# VHDCI.net
KiCad netlist of a schematic drawn in Altium Designer
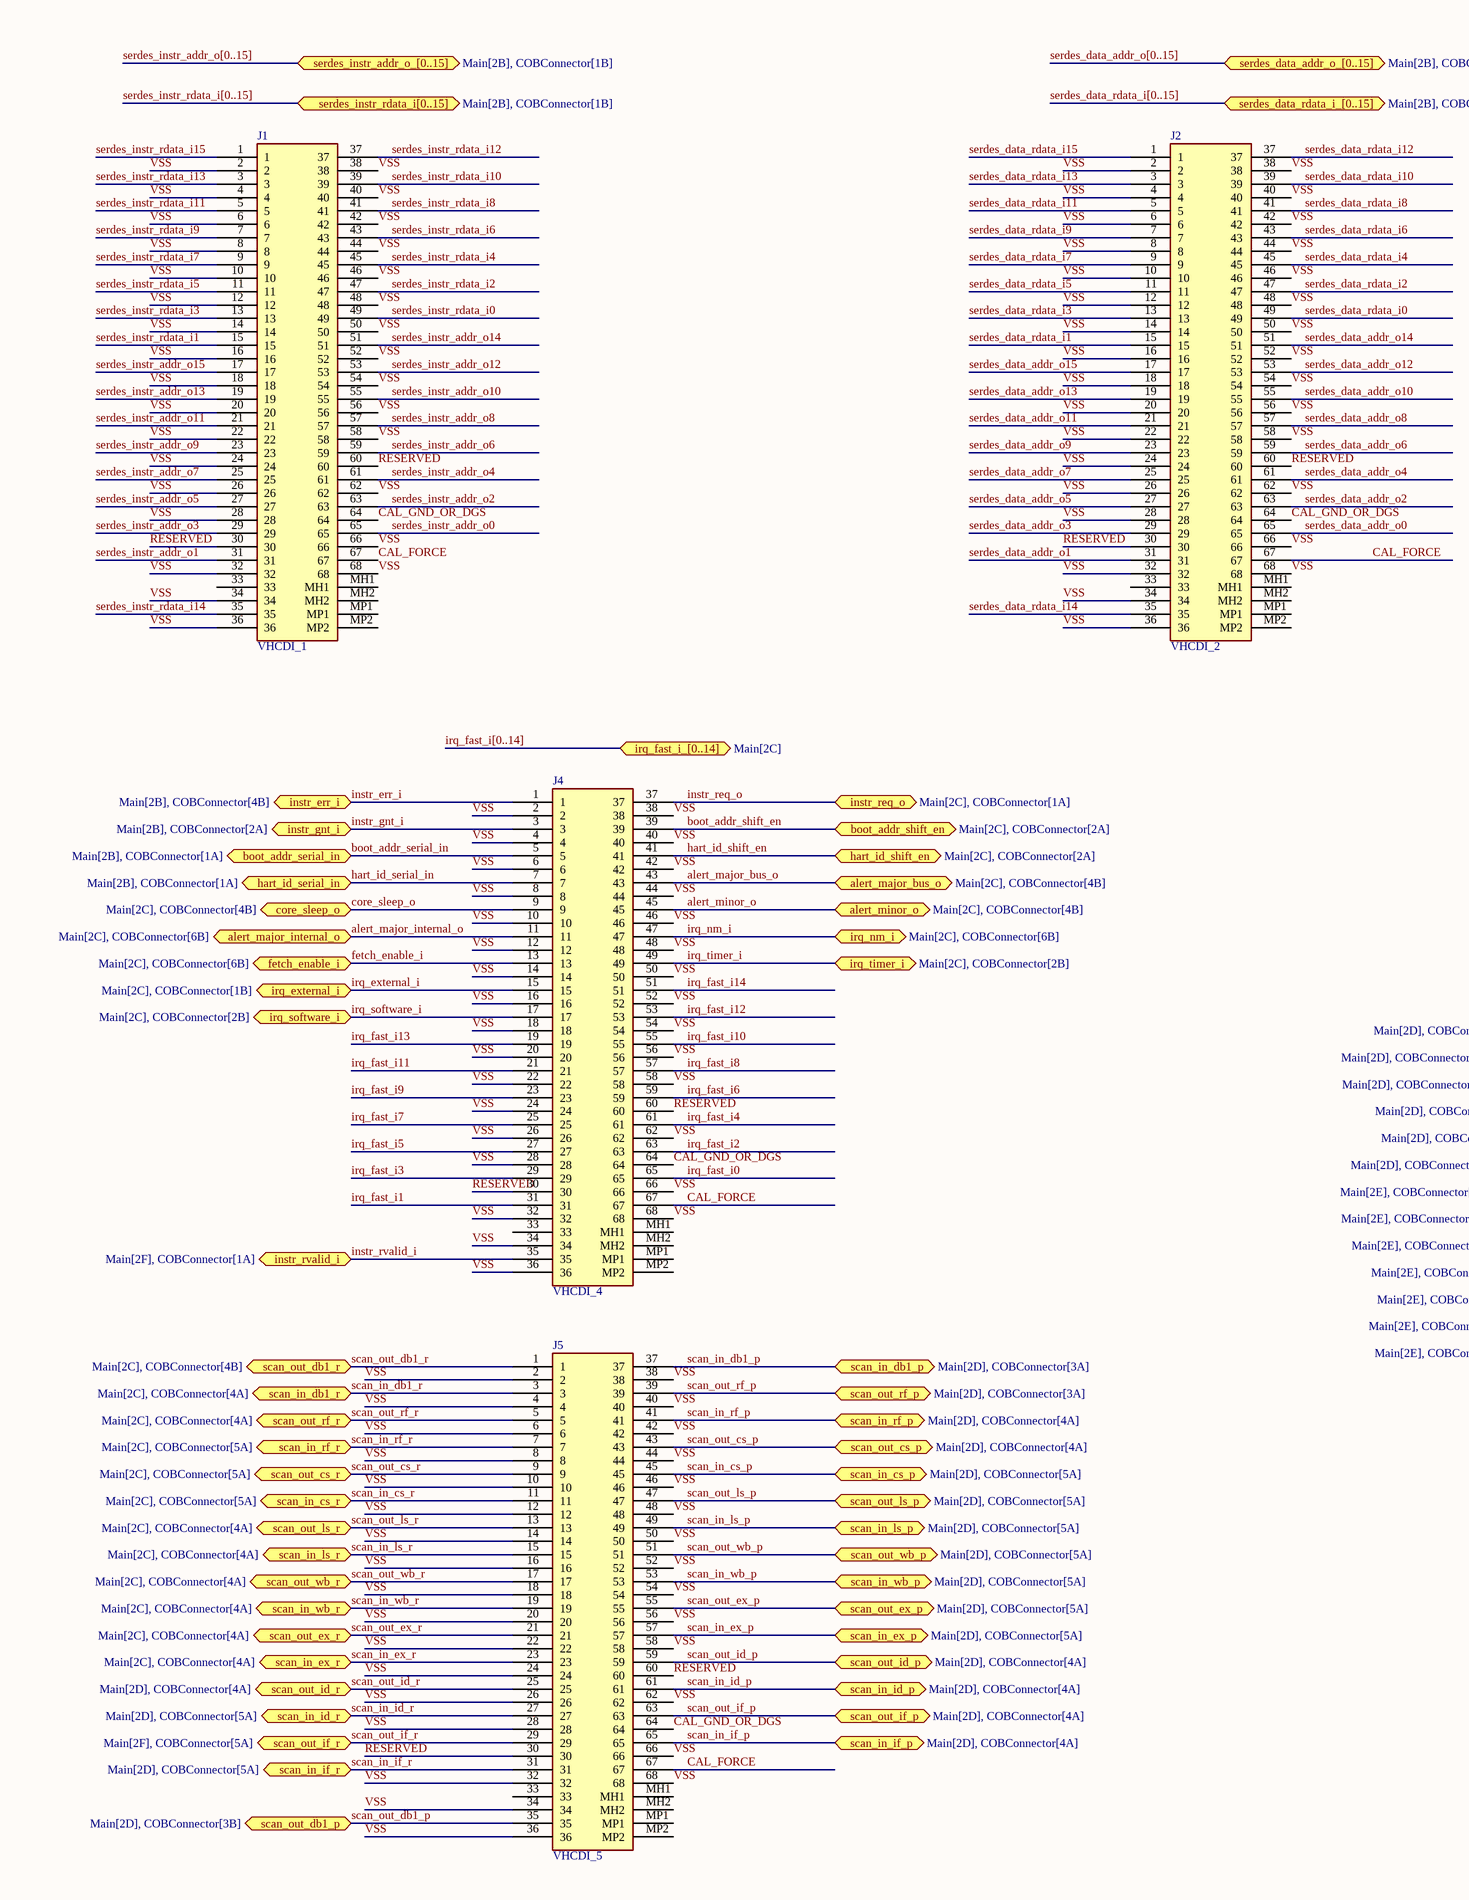
[diagram p0: VHDCI.SchDoc, left]
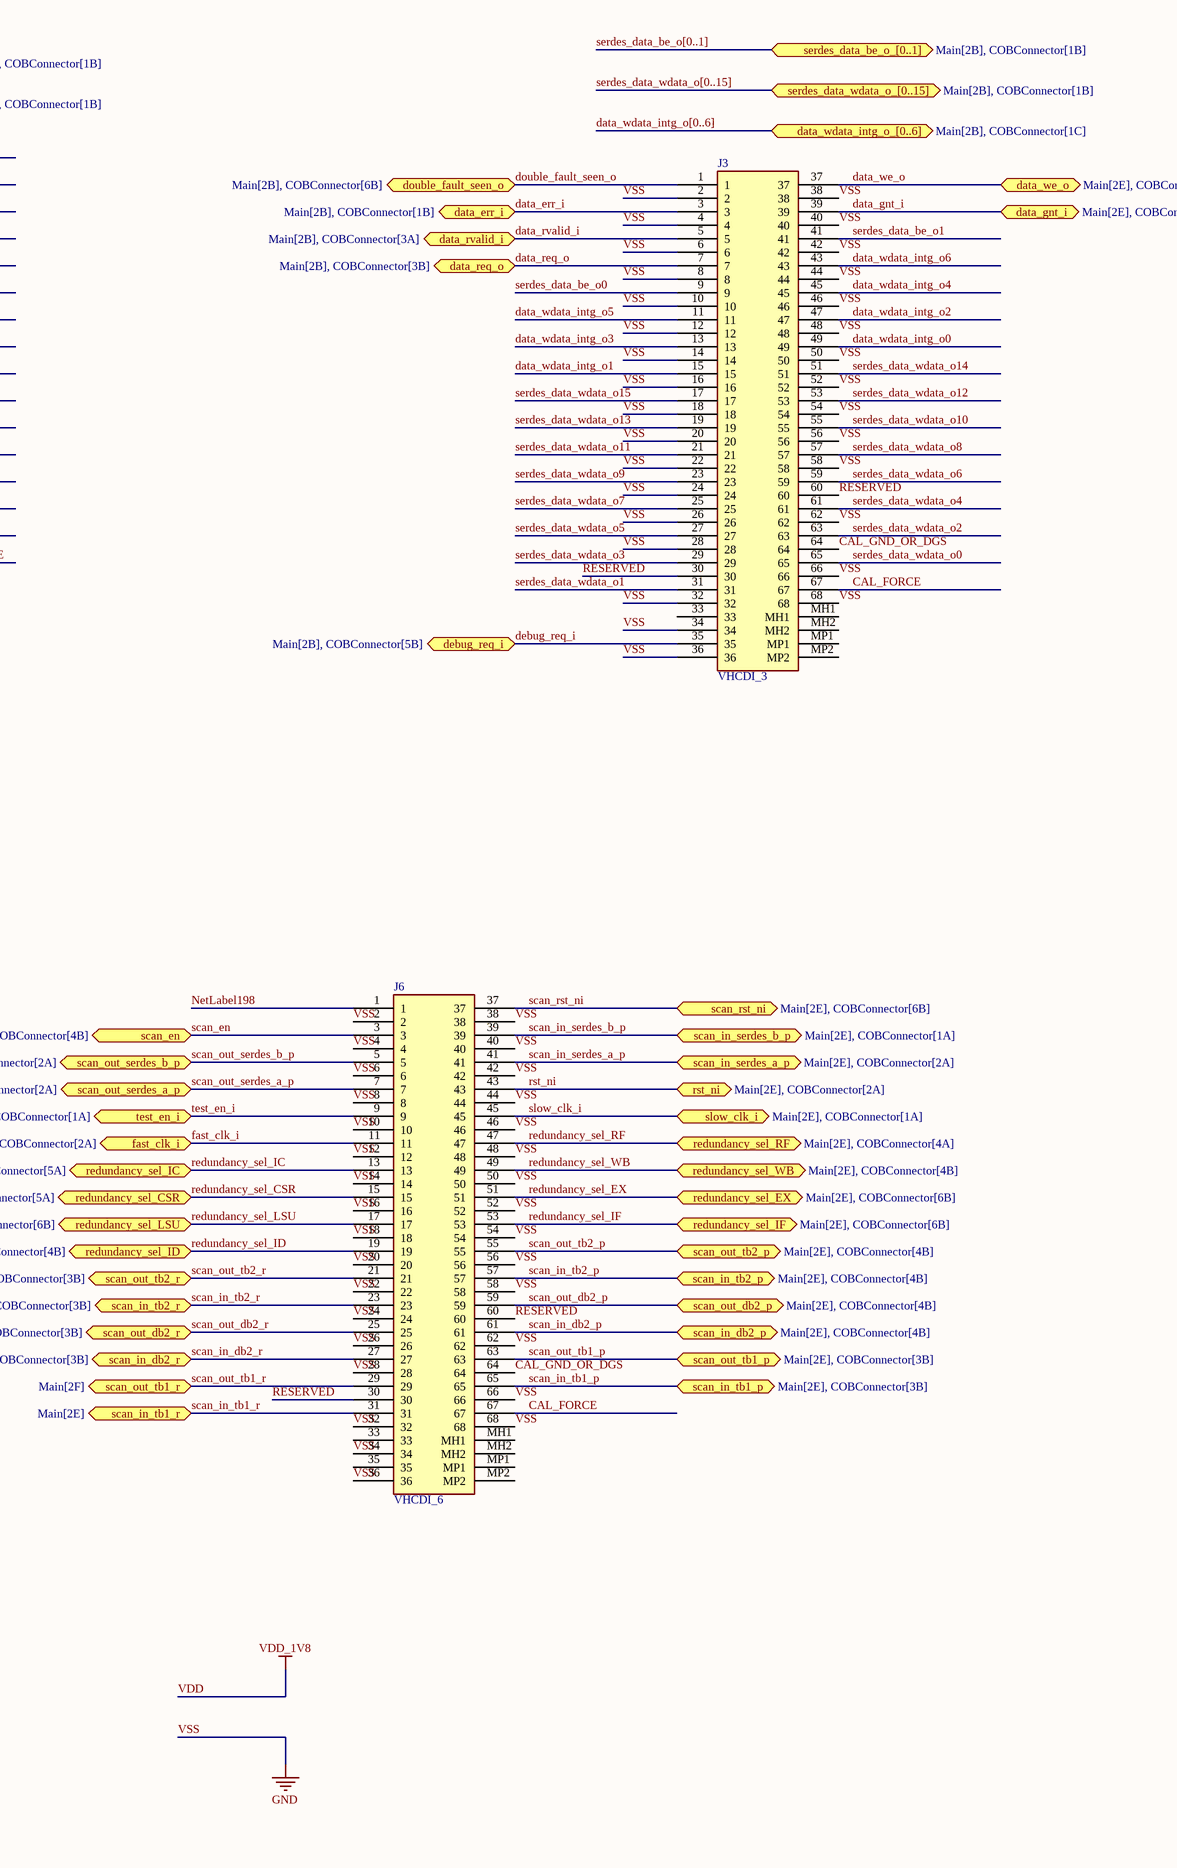
[diagram p1: VHDCI.SchDoc, right]

(export (version "E")
  (design (tool "Eeschema 10.0.6"))
  (components
    (comp (ref "J1")
      (value "VHCDI_1")
      (footprint "CONN68_HDRA-EC_HON")
      (description "Connector")
      (fields (field (name "MANUFACTURER_PART_NUMBER") "785633-01"))
      (libsource (lib "00-100001-001") (part "785633-01"))
    )
    (comp (ref "J2")
      (value "VHCDI_2")
      (footprint "CONN68_HDRA-EC_HON")
      (description "Connector")
      (fields (field (name "MANUFACTURER_PART_NUMBER") "785633-01"))
      (libsource (lib "00-100001-001") (part "785633-01"))
    )
    (comp (ref "J3")
      (value "VHCDI_3")
      (footprint "CONN68_HDRA-EC_HON")
      (description "Connector")
      (fields (field (name "MANUFACTURER_PART_NUMBER") "785633-01"))
      (libsource (lib "00-100001-001") (part "785633-01"))
    )
    (comp (ref "J4")
      (value "VHCDI_4")
      (footprint "CONN68_HDRA-EC_HON")
      (description "Connector")
      (fields (field (name "MANUFACTURER_PART_NUMBER") "785633-01"))
      (libsource (lib "00-100001-001") (part "785633-01"))
    )
    (comp (ref "J5")
      (value "VHCDI_5")
      (footprint "CONN68_HDRA-EC_HON")
      (description "Connector")
      (fields (field (name "MANUFACTURER_PART_NUMBER") "785633-01"))
      (libsource (lib "00-100001-001") (part "785633-01"))
    )
    (comp (ref "J6")
      (value "VHCDI_6")
      (footprint "CONN68_HDRA-EC_HON")
      (description "Connector")
      (fields (field (name "MANUFACTURER_PART_NUMBER") "785633-01"))
      (libsource (lib "00-100001-001") (part "785633-01"))
    )
  )
  (nets
    (net (code "1") (name "/CAL_FORCE") (class "Default")
      (node (ref "J1") (pin "67") (pinfunction "67_67") (pintype "passive"))
      (node (ref "J2") (pin "67") (pinfunction "67_67") (pintype "passive"))
      (node (ref "J3") (pin "67") (pinfunction "67_67") (pintype "passive"))
      (node (ref "J4") (pin "67") (pinfunction "67_67") (pintype "passive"))
      (node (ref "J5") (pin "67") (pinfunction "67_67") (pintype "passive"))
      (node (ref "J6") (pin "67") (pinfunction "67_67") (pintype "passive"))
    )
    (net (code "2") (name "/CAL_GND_OR_DGS") (class "Default")
      (node (ref "J1") (pin "64") (pinfunction "64_64") (pintype "passive"))
      (node (ref "J2") (pin "64") (pinfunction "64_64") (pintype "passive"))
      (node (ref "J3") (pin "64") (pinfunction "64_64") (pintype "passive"))
      (node (ref "J4") (pin "64") (pinfunction "64_64") (pintype "passive"))
      (node (ref "J5") (pin "64") (pinfunction "64_64") (pintype "passive"))
      (node (ref "J6") (pin "64") (pinfunction "64_64") (pintype "passive"))
    )
    (net (code "3") (name "/NetLabel198") (class "Default")
      (node (ref "J6") (pin "1") (pinfunction "1_1") (pintype "passive"))
    )
    (net (code "4") (name "/RESERVED") (class "Default")
      (node (ref "J1") (pin "30") (pinfunction "30_30") (pintype "passive"))
      (node (ref "J1") (pin "60") (pinfunction "60_60") (pintype "passive"))
      (node (ref "J2") (pin "30") (pinfunction "30_30") (pintype "passive"))
      (node (ref "J2") (pin "60") (pinfunction "60_60") (pintype "passive"))
      (node (ref "J3") (pin "30") (pinfunction "30_30") (pintype "passive"))
      (node (ref "J3") (pin "60") (pinfunction "60_60") (pintype "passive"))
      (node (ref "J4") (pin "30") (pinfunction "30_30") (pintype "passive"))
      (node (ref "J4") (pin "60") (pinfunction "60_60") (pintype "passive"))
      (node (ref "J5") (pin "30") (pinfunction "30_30") (pintype "passive"))
      (node (ref "J5") (pin "60") (pinfunction "60_60") (pintype "passive"))
      (node (ref "J6") (pin "30") (pinfunction "30_30") (pintype "passive"))
      (node (ref "J6") (pin "60") (pinfunction "60_60") (pintype "passive"))
    )
    (net (code "5") (name "/alert_major_bus_o") (class "Default")
      (node (ref "J4") (pin "43") (pinfunction "43_43") (pintype "passive"))
    )
    (net (code "6") (name "/alert_major_internal_o") (class "Default")
      (node (ref "J4") (pin "11") (pinfunction "11_11") (pintype "passive"))
    )
    (net (code "7") (name "/alert_minor_o") (class "Default")
      (node (ref "J4") (pin "45") (pinfunction "45_45") (pintype "passive"))
    )
    (net (code "8") (name "/boot_addr_serial_in") (class "Default")
      (node (ref "J4") (pin "5") (pinfunction "5_5") (pintype "passive"))
    )
    (net (code "9") (name "/boot_addr_shift_en") (class "Default")
      (node (ref "J4") (pin "39") (pinfunction "39_39") (pintype "passive"))
    )
    (net (code "10") (name "/core_sleep_o") (class "Default")
      (node (ref "J4") (pin "9") (pinfunction "9_9") (pintype "passive"))
    )
    (net (code "11") (name "/data_err_i") (class "Default")
      (node (ref "J3") (pin "3") (pinfunction "3_3") (pintype "passive"))
    )
    (net (code "12") (name "/data_gnt_i") (class "Default")
      (node (ref "J3") (pin "39") (pinfunction "39_39") (pintype "passive"))
    )
    (net (code "13") (name "/data_req_o") (class "Default")
      (node (ref "J3") (pin "7") (pinfunction "7_7") (pintype "passive"))
    )
    (net (code "14") (name "/data_rvalid_i") (class "Default")
      (node (ref "J3") (pin "5") (pinfunction "5_5") (pintype "passive"))
    )
    (net (code "15") (name "/data_wdata_intg_o0") (class "Default")
      (node (ref "J3") (pin "49") (pinfunction "49_49") (pintype "passive"))
    )
    (net (code "16") (name "/data_wdata_intg_o1") (class "Default")
      (node (ref "J3") (pin "15") (pinfunction "15_15") (pintype "passive"))
    )
    (net (code "17") (name "/data_wdata_intg_o2") (class "Default")
      (node (ref "J3") (pin "47") (pinfunction "47_47") (pintype "passive"))
    )
    (net (code "18") (name "/data_wdata_intg_o3") (class "Default")
      (node (ref "J3") (pin "13") (pinfunction "13_13") (pintype "passive"))
    )
    (net (code "19") (name "/data_wdata_intg_o4") (class "Default")
      (node (ref "J3") (pin "45") (pinfunction "45_45") (pintype "passive"))
    )
    (net (code "20") (name "/data_wdata_intg_o5") (class "Default")
      (node (ref "J3") (pin "11") (pinfunction "11_11") (pintype "passive"))
    )
    (net (code "21") (name "/data_wdata_intg_o6") (class "Default")
      (node (ref "J3") (pin "43") (pinfunction "43_43") (pintype "passive"))
    )
    (net (code "23") (name "/data_we_o") (class "Default")
      (node (ref "J3") (pin "37") (pinfunction "37_37") (pintype "passive"))
    )
    (net (code "24") (name "/debug_req_i") (class "Default")
      (node (ref "J3") (pin "35") (pinfunction "35_35") (pintype "passive"))
    )
    (net (code "25") (name "/double_fault_seen_o") (class "Default")
      (node (ref "J3") (pin "1") (pinfunction "1_1") (pintype "passive"))
    )
    (net (code "26") (name "/fast_clk_i") (class "Default")
      (node (ref "J6") (pin "11") (pinfunction "11_11") (pintype "passive"))
    )
    (net (code "27") (name "/fetch_enable_i") (class "Default")
      (node (ref "J4") (pin "13") (pinfunction "13_13") (pintype "passive"))
    )
    (net (code "28") (name "/hart_id_serial_in") (class "Default")
      (node (ref "J4") (pin "7") (pinfunction "7_7") (pintype "passive"))
    )
    (net (code "29") (name "/hart_id_shift_en") (class "Default")
      (node (ref "J4") (pin "41") (pinfunction "41_41") (pintype "passive"))
    )
    (net (code "30") (name "/instr_err_i") (class "Default")
      (node (ref "J4") (pin "1") (pinfunction "1_1") (pintype "passive"))
    )
    (net (code "31") (name "/instr_gnt_i") (class "Default")
      (node (ref "J4") (pin "3") (pinfunction "3_3") (pintype "passive"))
    )
    (net (code "32") (name "/instr_req_o") (class "Default")
      (node (ref "J4") (pin "37") (pinfunction "37_37") (pintype "passive"))
    )
    (net (code "33") (name "/instr_rvalid_i") (class "Default")
      (node (ref "J4") (pin "35") (pinfunction "35_35") (pintype "passive"))
    )
    (net (code "34") (name "/irq_external_i") (class "Default")
      (node (ref "J4") (pin "15") (pinfunction "15_15") (pintype "passive"))
    )
    (net (code "35") (name "/irq_fast_i0") (class "Default")
      (node (ref "J4") (pin "65") (pinfunction "65_65") (pintype "passive"))
    )
    (net (code "36") (name "/irq_fast_i1") (class "Default")
      (node (ref "J4") (pin "31") (pinfunction "31_31") (pintype "passive"))
    )
    (net (code "37") (name "/irq_fast_i2") (class "Default")
      (node (ref "J4") (pin "63") (pinfunction "63_63") (pintype "passive"))
    )
    (net (code "38") (name "/irq_fast_i3") (class "Default")
      (node (ref "J4") (pin "29") (pinfunction "29_29") (pintype "passive"))
    )
    (net (code "39") (name "/irq_fast_i4") (class "Default")
      (node (ref "J4") (pin "61") (pinfunction "61_61") (pintype "passive"))
    )
    (net (code "40") (name "/irq_fast_i5") (class "Default")
      (node (ref "J4") (pin "27") (pinfunction "27_27") (pintype "passive"))
    )
    (net (code "41") (name "/irq_fast_i6") (class "Default")
      (node (ref "J4") (pin "59") (pinfunction "59_59") (pintype "passive"))
    )
    (net (code "42") (name "/irq_fast_i7") (class "Default")
      (node (ref "J4") (pin "25") (pinfunction "25_25") (pintype "passive"))
    )
    (net (code "43") (name "/irq_fast_i8") (class "Default")
      (node (ref "J4") (pin "57") (pinfunction "57_57") (pintype "passive"))
    )
    (net (code "44") (name "/irq_fast_i9") (class "Default")
      (node (ref "J4") (pin "23") (pinfunction "23_23") (pintype "passive"))
    )
    (net (code "45") (name "/irq_fast_i10") (class "Default")
      (node (ref "J4") (pin "55") (pinfunction "55_55") (pintype "passive"))
    )
    (net (code "46") (name "/irq_fast_i11") (class "Default")
      (node (ref "J4") (pin "21") (pinfunction "21_21") (pintype "passive"))
    )
    (net (code "47") (name "/irq_fast_i12") (class "Default")
      (node (ref "J4") (pin "53") (pinfunction "53_53") (pintype "passive"))
    )
    (net (code "48") (name "/irq_fast_i13") (class "Default")
      (node (ref "J4") (pin "19") (pinfunction "19_19") (pintype "passive"))
    )
    (net (code "49") (name "/irq_fast_i14") (class "Default")
      (node (ref "J4") (pin "51") (pinfunction "51_51") (pintype "passive"))
    )
    (net (code "51") (name "/irq_nm_i") (class "Default")
      (node (ref "J4") (pin "47") (pinfunction "47_47") (pintype "passive"))
    )
    (net (code "52") (name "/irq_software_i") (class "Default")
      (node (ref "J4") (pin "17") (pinfunction "17_17") (pintype "passive"))
    )
    (net (code "53") (name "/irq_timer_i") (class "Default")
      (node (ref "J4") (pin "49") (pinfunction "49_49") (pintype "passive"))
    )
    (net (code "54") (name "/redundancy_sel_CSR") (class "Default")
      (node (ref "J6") (pin "15") (pinfunction "15_15") (pintype "passive"))
    )
    (net (code "55") (name "/redundancy_sel_EX") (class "Default")
      (node (ref "J6") (pin "51") (pinfunction "51_51") (pintype "passive"))
    )
    (net (code "56") (name "/redundancy_sel_IC") (class "Default")
      (node (ref "J6") (pin "13") (pinfunction "13_13") (pintype "passive"))
    )
    (net (code "57") (name "/redundancy_sel_ID") (class "Default")
      (node (ref "J6") (pin "19") (pinfunction "19_19") (pintype "passive"))
    )
    (net (code "58") (name "/redundancy_sel_IF") (class "Default")
      (node (ref "J6") (pin "53") (pinfunction "53_53") (pintype "passive"))
    )
    (net (code "59") (name "/redundancy_sel_LSU") (class "Default")
      (node (ref "J6") (pin "17") (pinfunction "17_17") (pintype "passive"))
    )
    (net (code "60") (name "/redundancy_sel_RF") (class "Default")
      (node (ref "J6") (pin "47") (pinfunction "47_47") (pintype "passive"))
    )
    (net (code "61") (name "/redundancy_sel_WB") (class "Default")
      (node (ref "J6") (pin "49") (pinfunction "49_49") (pintype "passive"))
    )
    (net (code "62") (name "/rst_ni") (class "Default")
      (node (ref "J6") (pin "43") (pinfunction "43_43") (pintype "passive"))
    )
    (net (code "63") (name "/scan_en") (class "Default")
      (node (ref "J6") (pin "3") (pinfunction "3_3") (pintype "passive"))
    )
    (net (code "64") (name "/scan_in_cs_p") (class "Default")
      (node (ref "J5") (pin "45") (pinfunction "45_45") (pintype "passive"))
    )
    (net (code "65") (name "/scan_in_cs_r") (class "Default")
      (node (ref "J5") (pin "11") (pinfunction "11_11") (pintype "passive"))
    )
    (net (code "66") (name "/scan_in_db1_p") (class "Default")
      (node (ref "J5") (pin "37") (pinfunction "37_37") (pintype "passive"))
    )
    (net (code "67") (name "/scan_in_db1_r") (class "Default")
      (node (ref "J5") (pin "3") (pinfunction "3_3") (pintype "passive"))
    )
    (net (code "68") (name "/scan_in_db2_p") (class "Default")
      (node (ref "J6") (pin "61") (pinfunction "61_61") (pintype "passive"))
    )
    (net (code "69") (name "/scan_in_db2_r") (class "Default")
      (node (ref "J6") (pin "27") (pinfunction "27_27") (pintype "passive"))
    )
    (net (code "70") (name "/scan_in_ex_p") (class "Default")
      (node (ref "J5") (pin "57") (pinfunction "57_57") (pintype "passive"))
    )
    (net (code "71") (name "/scan_in_ex_r") (class "Default")
      (node (ref "J5") (pin "23") (pinfunction "23_23") (pintype "passive"))
    )
    (net (code "72") (name "/scan_in_id_p") (class "Default")
      (node (ref "J5") (pin "61") (pinfunction "61_61") (pintype "passive"))
    )
    (net (code "73") (name "/scan_in_id_r") (class "Default")
      (node (ref "J5") (pin "27") (pinfunction "27_27") (pintype "passive"))
    )
    (net (code "74") (name "/scan_in_if_p") (class "Default")
      (node (ref "J5") (pin "65") (pinfunction "65_65") (pintype "passive"))
    )
    (net (code "75") (name "/scan_in_if_r") (class "Default")
      (node (ref "J5") (pin "31") (pinfunction "31_31") (pintype "passive"))
    )
    (net (code "76") (name "/scan_in_ls_p") (class "Default")
      (node (ref "J5") (pin "49") (pinfunction "49_49") (pintype "passive"))
    )
    (net (code "77") (name "/scan_in_ls_r") (class "Default")
      (node (ref "J5") (pin "15") (pinfunction "15_15") (pintype "passive"))
    )
    (net (code "78") (name "/scan_in_rf_p") (class "Default")
      (node (ref "J5") (pin "41") (pinfunction "41_41") (pintype "passive"))
    )
    (net (code "79") (name "/scan_in_rf_r") (class "Default")
      (node (ref "J5") (pin "7") (pinfunction "7_7") (pintype "passive"))
    )
    (net (code "80") (name "/scan_in_serdes_a_p") (class "Default")
      (node (ref "J6") (pin "41") (pinfunction "41_41") (pintype "passive"))
    )
    (net (code "81") (name "/scan_in_serdes_b_p") (class "Default")
      (node (ref "J6") (pin "39") (pinfunction "39_39") (pintype "passive"))
    )
    (net (code "82") (name "/scan_in_tb1_p") (class "Default")
      (node (ref "J6") (pin "65") (pinfunction "65_65") (pintype "passive"))
    )
    (net (code "83") (name "/scan_in_tb1_r") (class "Default")
      (node (ref "J6") (pin "31") (pinfunction "31_31") (pintype "passive"))
    )
    (net (code "84") (name "/scan_in_tb2_p") (class "Default")
      (node (ref "J6") (pin "57") (pinfunction "57_57") (pintype "passive"))
    )
    (net (code "85") (name "/scan_in_tb2_r") (class "Default")
      (node (ref "J6") (pin "23") (pinfunction "23_23") (pintype "passive"))
    )
    (net (code "86") (name "/scan_in_wb_p") (class "Default")
      (node (ref "J5") (pin "53") (pinfunction "53_53") (pintype "passive"))
    )
    (net (code "87") (name "/scan_in_wb_r") (class "Default")
      (node (ref "J5") (pin "19") (pinfunction "19_19") (pintype "passive"))
    )
    (net (code "88") (name "/scan_out_cs_p") (class "Default")
      (node (ref "J5") (pin "43") (pinfunction "43_43") (pintype "passive"))
    )
    (net (code "89") (name "/scan_out_cs_r") (class "Default")
      (node (ref "J5") (pin "9") (pinfunction "9_9") (pintype "passive"))
    )
    (net (code "90") (name "/scan_out_db1_p") (class "Default")
      (node (ref "J5") (pin "35") (pinfunction "35_35") (pintype "passive"))
    )
    (net (code "91") (name "/scan_out_db1_r") (class "Default")
      (node (ref "J5") (pin "1") (pinfunction "1_1") (pintype "passive"))
    )
    (net (code "92") (name "/scan_out_db2_p") (class "Default")
      (node (ref "J6") (pin "59") (pinfunction "59_59") (pintype "passive"))
    )
    (net (code "93") (name "/scan_out_db2_r") (class "Default")
      (node (ref "J6") (pin "25") (pinfunction "25_25") (pintype "passive"))
    )
    (net (code "94") (name "/scan_out_ex_p") (class "Default")
      (node (ref "J5") (pin "55") (pinfunction "55_55") (pintype "passive"))
    )
    (net (code "95") (name "/scan_out_ex_r") (class "Default")
      (node (ref "J5") (pin "21") (pinfunction "21_21") (pintype "passive"))
    )
    (net (code "96") (name "/scan_out_id_p") (class "Default")
      (node (ref "J5") (pin "59") (pinfunction "59_59") (pintype "passive"))
    )
    (net (code "97") (name "/scan_out_id_r") (class "Default")
      (node (ref "J5") (pin "25") (pinfunction "25_25") (pintype "passive"))
    )
    (net (code "98") (name "/scan_out_if_p") (class "Default")
      (node (ref "J5") (pin "63") (pinfunction "63_63") (pintype "passive"))
    )
    (net (code "99") (name "/scan_out_if_r") (class "Default")
      (node (ref "J5") (pin "29") (pinfunction "29_29") (pintype "passive"))
    )
    (net (code "100") (name "/scan_out_ls_p") (class "Default")
      (node (ref "J5") (pin "47") (pinfunction "47_47") (pintype "passive"))
    )
    (net (code "101") (name "/scan_out_ls_r") (class "Default")
      (node (ref "J5") (pin "13") (pinfunction "13_13") (pintype "passive"))
    )
    (net (code "102") (name "/scan_out_rf_p") (class "Default")
      (node (ref "J5") (pin "39") (pinfunction "39_39") (pintype "passive"))
    )
    (net (code "103") (name "/scan_out_rf_r") (class "Default")
      (node (ref "J5") (pin "5") (pinfunction "5_5") (pintype "passive"))
    )
    (net (code "104") (name "/scan_out_serdes_a_p") (class "Default")
      (node (ref "J6") (pin "7") (pinfunction "7_7") (pintype "passive"))
    )
    (net (code "105") (name "/scan_out_serdes_b_p") (class "Default")
      (node (ref "J6") (pin "5") (pinfunction "5_5") (pintype "passive"))
    )
    (net (code "106") (name "/scan_out_tb1_p") (class "Default")
      (node (ref "J6") (pin "63") (pinfunction "63_63") (pintype "passive"))
    )
    (net (code "107") (name "/scan_out_tb1_r") (class "Default")
      (node (ref "J6") (pin "29") (pinfunction "29_29") (pintype "passive"))
    )
    (net (code "108") (name "/scan_out_tb2_p") (class "Default")
      (node (ref "J6") (pin "55") (pinfunction "55_55") (pintype "passive"))
    )
    (net (code "109") (name "/scan_out_tb2_r") (class "Default")
      (node (ref "J6") (pin "21") (pinfunction "21_21") (pintype "passive"))
    )
    (net (code "110") (name "/scan_out_wb_p") (class "Default")
      (node (ref "J5") (pin "51") (pinfunction "51_51") (pintype "passive"))
    )
    (net (code "111") (name "/scan_out_wb_r") (class "Default")
      (node (ref "J5") (pin "17") (pinfunction "17_17") (pintype "passive"))
    )
    (net (code "112") (name "/scan_rst_ni") (class "Default")
      (node (ref "J6") (pin "37") (pinfunction "37_37") (pintype "passive"))
    )
    (net (code "113") (name "/serdes_data_addr_o0") (class "Default")
      (node (ref "J2") (pin "65") (pinfunction "65_65") (pintype "passive"))
    )
    (net (code "114") (name "/serdes_data_addr_o1") (class "Default")
      (node (ref "J2") (pin "31") (pinfunction "31_31") (pintype "passive"))
    )
    (net (code "115") (name "/serdes_data_addr_o2") (class "Default")
      (node (ref "J2") (pin "63") (pinfunction "63_63") (pintype "passive"))
    )
    (net (code "116") (name "/serdes_data_addr_o3") (class "Default")
      (node (ref "J2") (pin "29") (pinfunction "29_29") (pintype "passive"))
    )
    (net (code "117") (name "/serdes_data_addr_o4") (class "Default")
      (node (ref "J2") (pin "61") (pinfunction "61_61") (pintype "passive"))
    )
    (net (code "118") (name "/serdes_data_addr_o5") (class "Default")
      (node (ref "J2") (pin "27") (pinfunction "27_27") (pintype "passive"))
    )
    (net (code "119") (name "/serdes_data_addr_o6") (class "Default")
      (node (ref "J2") (pin "59") (pinfunction "59_59") (pintype "passive"))
    )
    (net (code "120") (name "/serdes_data_addr_o7") (class "Default")
      (node (ref "J2") (pin "25") (pinfunction "25_25") (pintype "passive"))
    )
    (net (code "121") (name "/serdes_data_addr_o8") (class "Default")
      (node (ref "J2") (pin "57") (pinfunction "57_57") (pintype "passive"))
    )
    (net (code "122") (name "/serdes_data_addr_o9") (class "Default")
      (node (ref "J2") (pin "23") (pinfunction "23_23") (pintype "passive"))
    )
    (net (code "123") (name "/serdes_data_addr_o10") (class "Default")
      (node (ref "J2") (pin "55") (pinfunction "55_55") (pintype "passive"))
    )
    (net (code "124") (name "/serdes_data_addr_o11") (class "Default")
      (node (ref "J2") (pin "21") (pinfunction "21_21") (pintype "passive"))
    )
    (net (code "125") (name "/serdes_data_addr_o12") (class "Default")
      (node (ref "J2") (pin "53") (pinfunction "53_53") (pintype "passive"))
    )
    (net (code "126") (name "/serdes_data_addr_o13") (class "Default")
      (node (ref "J2") (pin "19") (pinfunction "19_19") (pintype "passive"))
    )
    (net (code "127") (name "/serdes_data_addr_o14") (class "Default")
      (node (ref "J2") (pin "51") (pinfunction "51_51") (pintype "passive"))
    )
    (net (code "128") (name "/serdes_data_addr_o15") (class "Default")
      (node (ref "J2") (pin "17") (pinfunction "17_17") (pintype "passive"))
    )
    (net (code "130") (name "/serdes_data_be_o0") (class "Default")
      (node (ref "J3") (pin "9") (pinfunction "9_9") (pintype "passive"))
    )
    (net (code "131") (name "/serdes_data_be_o1") (class "Default")
      (node (ref "J3") (pin "41") (pinfunction "41_41") (pintype "passive"))
    )
    (net (code "133") (name "/serdes_data_rdata_i0") (class "Default")
      (node (ref "J2") (pin "49") (pinfunction "49_49") (pintype "passive"))
    )
    (net (code "134") (name "/serdes_data_rdata_i1") (class "Default")
      (node (ref "J2") (pin "15") (pinfunction "15_15") (pintype "passive"))
    )
    (net (code "135") (name "/serdes_data_rdata_i2") (class "Default")
      (node (ref "J2") (pin "47") (pinfunction "47_47") (pintype "passive"))
    )
    (net (code "136") (name "/serdes_data_rdata_i3") (class "Default")
      (node (ref "J2") (pin "13") (pinfunction "13_13") (pintype "passive"))
    )
    (net (code "137") (name "/serdes_data_rdata_i4") (class "Default")
      (node (ref "J2") (pin "45") (pinfunction "45_45") (pintype "passive"))
    )
    (net (code "138") (name "/serdes_data_rdata_i5") (class "Default")
      (node (ref "J2") (pin "11") (pinfunction "11_11") (pintype "passive"))
    )
    (net (code "139") (name "/serdes_data_rdata_i6") (class "Default")
      (node (ref "J2") (pin "43") (pinfunction "43_43") (pintype "passive"))
    )
    (net (code "140") (name "/serdes_data_rdata_i7") (class "Default")
      (node (ref "J2") (pin "9") (pinfunction "9_9") (pintype "passive"))
    )
    (net (code "141") (name "/serdes_data_rdata_i8") (class "Default")
      (node (ref "J2") (pin "41") (pinfunction "41_41") (pintype "passive"))
    )
    (net (code "142") (name "/serdes_data_rdata_i9") (class "Default")
      (node (ref "J2") (pin "7") (pinfunction "7_7") (pintype "passive"))
    )
    (net (code "143") (name "/serdes_data_rdata_i10") (class "Default")
      (node (ref "J2") (pin "39") (pinfunction "39_39") (pintype "passive"))
    )
    (net (code "144") (name "/serdes_data_rdata_i11") (class "Default")
      (node (ref "J2") (pin "5") (pinfunction "5_5") (pintype "passive"))
    )
    (net (code "145") (name "/serdes_data_rdata_i12") (class "Default")
      (node (ref "J2") (pin "37") (pinfunction "37_37") (pintype "passive"))
    )
    (net (code "146") (name "/serdes_data_rdata_i13") (class "Default")
      (node (ref "J2") (pin "3") (pinfunction "3_3") (pintype "passive"))
    )
    (net (code "147") (name "/serdes_data_rdata_i14") (class "Default")
      (node (ref "J2") (pin "35") (pinfunction "35_35") (pintype "passive"))
    )
    (net (code "148") (name "/serdes_data_rdata_i15") (class "Default")
      (node (ref "J2") (pin "1") (pinfunction "1_1") (pintype "passive"))
    )
    (net (code "150") (name "/serdes_data_wdata_o0") (class "Default")
      (node (ref "J3") (pin "65") (pinfunction "65_65") (pintype "passive"))
    )
    (net (code "151") (name "/serdes_data_wdata_o1") (class "Default")
      (node (ref "J3") (pin "31") (pinfunction "31_31") (pintype "passive"))
    )
    (net (code "152") (name "/serdes_data_wdata_o2") (class "Default")
      (node (ref "J3") (pin "63") (pinfunction "63_63") (pintype "passive"))
    )
    (net (code "153") (name "/serdes_data_wdata_o3") (class "Default")
      (node (ref "J3") (pin "29") (pinfunction "29_29") (pintype "passive"))
    )
    (net (code "154") (name "/serdes_data_wdata_o4") (class "Default")
      (node (ref "J3") (pin "61") (pinfunction "61_61") (pintype "passive"))
    )
    (net (code "155") (name "/serdes_data_wdata_o5") (class "Default")
      (node (ref "J3") (pin "27") (pinfunction "27_27") (pintype "passive"))
    )
    (net (code "156") (name "/serdes_data_wdata_o6") (class "Default")
      (node (ref "J3") (pin "59") (pinfunction "59_59") (pintype "passive"))
    )
    (net (code "157") (name "/serdes_data_wdata_o7") (class "Default")
      (node (ref "J3") (pin "25") (pinfunction "25_25") (pintype "passive"))
    )
    (net (code "158") (name "/serdes_data_wdata_o8") (class "Default")
      (node (ref "J3") (pin "57") (pinfunction "57_57") (pintype "passive"))
    )
    (net (code "159") (name "/serdes_data_wdata_o9") (class "Default")
      (node (ref "J3") (pin "23") (pinfunction "23_23") (pintype "passive"))
    )
    (net (code "160") (name "/serdes_data_wdata_o10") (class "Default")
      (node (ref "J3") (pin "55") (pinfunction "55_55") (pintype "passive"))
    )
    (net (code "161") (name "/serdes_data_wdata_o11") (class "Default")
      (node (ref "J3") (pin "21") (pinfunction "21_21") (pintype "passive"))
    )
    (net (code "162") (name "/serdes_data_wdata_o12") (class "Default")
      (node (ref "J3") (pin "53") (pinfunction "53_53") (pintype "passive"))
    )
    (net (code "163") (name "/serdes_data_wdata_o13") (class "Default")
      (node (ref "J3") (pin "19") (pinfunction "19_19") (pintype "passive"))
    )
    (net (code "164") (name "/serdes_data_wdata_o14") (class "Default")
      (node (ref "J3") (pin "51") (pinfunction "51_51") (pintype "passive"))
    )
    (net (code "165") (name "/serdes_data_wdata_o15") (class "Default")
      (node (ref "J3") (pin "17") (pinfunction "17_17") (pintype "passive"))
    )
    (net (code "167") (name "/serdes_instr_addr_o0") (class "Default")
      (node (ref "J1") (pin "65") (pinfunction "65_65") (pintype "passive"))
    )
    (net (code "168") (name "/serdes_instr_addr_o1") (class "Default")
      (node (ref "J1") (pin "31") (pinfunction "31_31") (pintype "passive"))
    )
    (net (code "169") (name "/serdes_instr_addr_o2") (class "Default")
      (node (ref "J1") (pin "63") (pinfunction "63_63") (pintype "passive"))
    )
    (net (code "170") (name "/serdes_instr_addr_o3") (class "Default")
      (node (ref "J1") (pin "29") (pinfunction "29_29") (pintype "passive"))
    )
    (net (code "171") (name "/serdes_instr_addr_o4") (class "Default")
      (node (ref "J1") (pin "61") (pinfunction "61_61") (pintype "passive"))
    )
    (net (code "172") (name "/serdes_instr_addr_o5") (class "Default")
      (node (ref "J1") (pin "27") (pinfunction "27_27") (pintype "passive"))
    )
    (net (code "173") (name "/serdes_instr_addr_o6") (class "Default")
      (node (ref "J1") (pin "59") (pinfunction "59_59") (pintype "passive"))
    )
    (net (code "174") (name "/serdes_instr_addr_o7") (class "Default")
      (node (ref "J1") (pin "25") (pinfunction "25_25") (pintype "passive"))
    )
    (net (code "175") (name "/serdes_instr_addr_o8") (class "Default")
      (node (ref "J1") (pin "57") (pinfunction "57_57") (pintype "passive"))
    )
    (net (code "176") (name "/serdes_instr_addr_o9") (class "Default")
      (node (ref "J1") (pin "23") (pinfunction "23_23") (pintype "passive"))
    )
    (net (code "177") (name "/serdes_instr_addr_o10") (class "Default")
      (node (ref "J1") (pin "55") (pinfunction "55_55") (pintype "passive"))
    )
    (net (code "178") (name "/serdes_instr_addr_o11") (class "Default")
      (node (ref "J1") (pin "21") (pinfunction "21_21") (pintype "passive"))
    )
    (net (code "179") (name "/serdes_instr_addr_o12") (class "Default")
      (node (ref "J1") (pin "53") (pinfunction "53_53") (pintype "passive"))
    )
    (net (code "180") (name "/serdes_instr_addr_o13") (class "Default")
      (node (ref "J1") (pin "19") (pinfunction "19_19") (pintype "passive"))
    )
    (net (code "181") (name "/serdes_instr_addr_o14") (class "Default")
      (node (ref "J1") (pin "51") (pinfunction "51_51") (pintype "passive"))
    )
    (net (code "182") (name "/serdes_instr_addr_o15") (class "Default")
      (node (ref "J1") (pin "17") (pinfunction "17_17") (pintype "passive"))
    )
    (net (code "184") (name "/serdes_instr_rdata_i0") (class "Default")
      (node (ref "J1") (pin "49") (pinfunction "49_49") (pintype "passive"))
    )
    (net (code "185") (name "/serdes_instr_rdata_i1") (class "Default")
      (node (ref "J1") (pin "15") (pinfunction "15_15") (pintype "passive"))
    )
    (net (code "186") (name "/serdes_instr_rdata_i2") (class "Default")
      (node (ref "J1") (pin "47") (pinfunction "47_47") (pintype "passive"))
    )
    (net (code "187") (name "/serdes_instr_rdata_i3") (class "Default")
      (node (ref "J1") (pin "13") (pinfunction "13_13") (pintype "passive"))
    )
    (net (code "188") (name "/serdes_instr_rdata_i4") (class "Default")
      (node (ref "J1") (pin "45") (pinfunction "45_45") (pintype "passive"))
    )
    (net (code "189") (name "/serdes_instr_rdata_i5") (class "Default")
      (node (ref "J1") (pin "11") (pinfunction "11_11") (pintype "passive"))
    )
    (net (code "190") (name "/serdes_instr_rdata_i6") (class "Default")
      (node (ref "J1") (pin "43") (pinfunction "43_43") (pintype "passive"))
    )
    (net (code "191") (name "/serdes_instr_rdata_i7") (class "Default")
      (node (ref "J1") (pin "9") (pinfunction "9_9") (pintype "passive"))
    )
    (net (code "192") (name "/serdes_instr_rdata_i8") (class "Default")
      (node (ref "J1") (pin "41") (pinfunction "41_41") (pintype "passive"))
    )
    (net (code "193") (name "/serdes_instr_rdata_i9") (class "Default")
      (node (ref "J1") (pin "7") (pinfunction "7_7") (pintype "passive"))
    )
    (net (code "194") (name "/serdes_instr_rdata_i10") (class "Default")
      (node (ref "J1") (pin "39") (pinfunction "39_39") (pintype "passive"))
    )
    (net (code "195") (name "/serdes_instr_rdata_i11") (class "Default")
      (node (ref "J1") (pin "5") (pinfunction "5_5") (pintype "passive"))
    )
    (net (code "196") (name "/serdes_instr_rdata_i12") (class "Default")
      (node (ref "J1") (pin "37") (pinfunction "37_37") (pintype "passive"))
    )
    (net (code "197") (name "/serdes_instr_rdata_i13") (class "Default")
      (node (ref "J1") (pin "3") (pinfunction "3_3") (pintype "passive"))
    )
    (net (code "198") (name "/serdes_instr_rdata_i14") (class "Default")
      (node (ref "J1") (pin "35") (pinfunction "35_35") (pintype "passive"))
    )
    (net (code "199") (name "/serdes_instr_rdata_i15") (class "Default")
      (node (ref "J1") (pin "1") (pinfunction "1_1") (pintype "passive"))
    )
    (net (code "201") (name "/slow_clk_i") (class "Default")
      (node (ref "J6") (pin "45") (pinfunction "45_45") (pintype "passive"))
    )
    (net (code "202") (name "/test_en_i") (class "Default")
      (node (ref "J6") (pin "9") (pinfunction "9_9") (pintype "passive"))
    )
    (net (code "203") (name "GND") (class "Default")
      (node (ref "J1") (pin "10") (pinfunction "10_10") (pintype "passive"))
      (node (ref "J1") (pin "12") (pinfunction "12_12") (pintype "passive"))
      (node (ref "J1") (pin "14") (pinfunction "14_14") (pintype "passive"))
      (node (ref "J1") (pin "16") (pinfunction "16_16") (pintype "passive"))
      (node (ref "J1") (pin "18") (pinfunction "18_18") (pintype "passive"))
      (node (ref "J1") (pin "2") (pinfunction "2_2") (pintype "passive"))
      (node (ref "J1") (pin "20") (pinfunction "20_20") (pintype "passive"))
      (node (ref "J1") (pin "22") (pinfunction "22_22") (pintype "passive"))
      (node (ref "J1") (pin "24") (pinfunction "24_24") (pintype "passive"))
      (node (ref "J1") (pin "26") (pinfunction "26_26") (pintype "passive"))
      (node (ref "J1") (pin "28") (pinfunction "28_28") (pintype "passive"))
      (node (ref "J1") (pin "32") (pinfunction "32_32") (pintype "passive"))
      (node (ref "J1") (pin "34") (pinfunction "34_34") (pintype "passive"))
      (node (ref "J1") (pin "36") (pinfunction "36_36") (pintype "passive"))
      (node (ref "J1") (pin "38") (pinfunction "38_38") (pintype "passive"))
      (node (ref "J1") (pin "4") (pinfunction "4_4") (pintype "passive"))
      (node (ref "J1") (pin "40") (pinfunction "40_40") (pintype "passive"))
      (node (ref "J1") (pin "42") (pinfunction "42_42") (pintype "passive"))
      (node (ref "J1") (pin "44") (pinfunction "44_44") (pintype "passive"))
      (node (ref "J1") (pin "46") (pinfunction "46_46") (pintype "passive"))
      (node (ref "J1") (pin "48") (pinfunction "48_48") (pintype "passive"))
      (node (ref "J1") (pin "50") (pinfunction "50_50") (pintype "passive"))
      (node (ref "J1") (pin "52") (pinfunction "52_52") (pintype "passive"))
      (node (ref "J1") (pin "54") (pinfunction "54_54") (pintype "passive"))
      (node (ref "J1") (pin "56") (pinfunction "56_56") (pintype "passive"))
      (node (ref "J1") (pin "58") (pinfunction "58_58") (pintype "passive"))
      (node (ref "J1") (pin "6") (pinfunction "6_6") (pintype "passive"))
      (node (ref "J1") (pin "62") (pinfunction "62_62") (pintype "passive"))
      (node (ref "J1") (pin "66") (pinfunction "66_66") (pintype "passive"))
      (node (ref "J1") (pin "68") (pinfunction "68_68") (pintype "passive"))
      (node (ref "J1") (pin "8") (pinfunction "8_8") (pintype "passive"))
      (node (ref "J2") (pin "10") (pinfunction "10_10") (pintype "passive"))
      (node (ref "J2") (pin "12") (pinfunction "12_12") (pintype "passive"))
      (node (ref "J2") (pin "14") (pinfunction "14_14") (pintype "passive"))
      (node (ref "J2") (pin "16") (pinfunction "16_16") (pintype "passive"))
      (node (ref "J2") (pin "18") (pinfunction "18_18") (pintype "passive"))
      (node (ref "J2") (pin "2") (pinfunction "2_2") (pintype "passive"))
      (node (ref "J2") (pin "20") (pinfunction "20_20") (pintype "passive"))
      (node (ref "J2") (pin "22") (pinfunction "22_22") (pintype "passive"))
      (node (ref "J2") (pin "24") (pinfunction "24_24") (pintype "passive"))
      (node (ref "J2") (pin "26") (pinfunction "26_26") (pintype "passive"))
      (node (ref "J2") (pin "28") (pinfunction "28_28") (pintype "passive"))
      (node (ref "J2") (pin "32") (pinfunction "32_32") (pintype "passive"))
      (node (ref "J2") (pin "34") (pinfunction "34_34") (pintype "passive"))
      (node (ref "J2") (pin "36") (pinfunction "36_36") (pintype "passive"))
      (node (ref "J2") (pin "38") (pinfunction "38_38") (pintype "passive"))
      (node (ref "J2") (pin "4") (pinfunction "4_4") (pintype "passive"))
      (node (ref "J2") (pin "40") (pinfunction "40_40") (pintype "passive"))
      (node (ref "J2") (pin "42") (pinfunction "42_42") (pintype "passive"))
      (node (ref "J2") (pin "44") (pinfunction "44_44") (pintype "passive"))
      (node (ref "J2") (pin "46") (pinfunction "46_46") (pintype "passive"))
      (node (ref "J2") (pin "48") (pinfunction "48_48") (pintype "passive"))
      (node (ref "J2") (pin "50") (pinfunction "50_50") (pintype "passive"))
      (node (ref "J2") (pin "52") (pinfunction "52_52") (pintype "passive"))
      (node (ref "J2") (pin "54") (pinfunction "54_54") (pintype "passive"))
      (node (ref "J2") (pin "56") (pinfunction "56_56") (pintype "passive"))
      (node (ref "J2") (pin "58") (pinfunction "58_58") (pintype "passive"))
      (node (ref "J2") (pin "6") (pinfunction "6_6") (pintype "passive"))
      (node (ref "J2") (pin "62") (pinfunction "62_62") (pintype "passive"))
      (node (ref "J2") (pin "66") (pinfunction "66_66") (pintype "passive"))
      (node (ref "J2") (pin "68") (pinfunction "68_68") (pintype "passive"))
      (node (ref "J2") (pin "8") (pinfunction "8_8") (pintype "passive"))
      (node (ref "J3") (pin "10") (pinfunction "10_10") (pintype "passive"))
      (node (ref "J3") (pin "12") (pinfunction "12_12") (pintype "passive"))
      (node (ref "J3") (pin "14") (pinfunction "14_14") (pintype "passive"))
      (node (ref "J3") (pin "16") (pinfunction "16_16") (pintype "passive"))
      (node (ref "J3") (pin "18") (pinfunction "18_18") (pintype "passive"))
      (node (ref "J3") (pin "2") (pinfunction "2_2") (pintype "passive"))
      (node (ref "J3") (pin "20") (pinfunction "20_20") (pintype "passive"))
      (node (ref "J3") (pin "22") (pinfunction "22_22") (pintype "passive"))
      (node (ref "J3") (pin "24") (pinfunction "24_24") (pintype "passive"))
      (node (ref "J3") (pin "26") (pinfunction "26_26") (pintype "passive"))
      (node (ref "J3") (pin "28") (pinfunction "28_28") (pintype "passive"))
      (node (ref "J3") (pin "32") (pinfunction "32_32") (pintype "passive"))
      (node (ref "J3") (pin "34") (pinfunction "34_34") (pintype "passive"))
      (node (ref "J3") (pin "36") (pinfunction "36_36") (pintype "passive"))
      (node (ref "J3") (pin "38") (pinfunction "38_38") (pintype "passive"))
      (node (ref "J3") (pin "4") (pinfunction "4_4") (pintype "passive"))
      (node (ref "J3") (pin "40") (pinfunction "40_40") (pintype "passive"))
      (node (ref "J3") (pin "42") (pinfunction "42_42") (pintype "passive"))
      (node (ref "J3") (pin "44") (pinfunction "44_44") (pintype "passive"))
      (node (ref "J3") (pin "46") (pinfunction "46_46") (pintype "passive"))
      (node (ref "J3") (pin "48") (pinfunction "48_48") (pintype "passive"))
      (node (ref "J3") (pin "50") (pinfunction "50_50") (pintype "passive"))
      (node (ref "J3") (pin "52") (pinfunction "52_52") (pintype "passive"))
      (node (ref "J3") (pin "54") (pinfunction "54_54") (pintype "passive"))
      (node (ref "J3") (pin "56") (pinfunction "56_56") (pintype "passive"))
      (node (ref "J3") (pin "58") (pinfunction "58_58") (pintype "passive"))
      (node (ref "J3") (pin "6") (pinfunction "6_6") (pintype "passive"))
      (node (ref "J3") (pin "62") (pinfunction "62_62") (pintype "passive"))
      (node (ref "J3") (pin "66") (pinfunction "66_66") (pintype "passive"))
      (node (ref "J3") (pin "68") (pinfunction "68_68") (pintype "passive"))
      (node (ref "J3") (pin "8") (pinfunction "8_8") (pintype "passive"))
      (node (ref "J4") (pin "10") (pinfunction "10_10") (pintype "passive"))
      (node (ref "J4") (pin "12") (pinfunction "12_12") (pintype "passive"))
      (node (ref "J4") (pin "14") (pinfunction "14_14") (pintype "passive"))
      (node (ref "J4") (pin "16") (pinfunction "16_16") (pintype "passive"))
      (node (ref "J4") (pin "18") (pinfunction "18_18") (pintype "passive"))
      (node (ref "J4") (pin "2") (pinfunction "2_2") (pintype "passive"))
      (node (ref "J4") (pin "20") (pinfunction "20_20") (pintype "passive"))
      (node (ref "J4") (pin "22") (pinfunction "22_22") (pintype "passive"))
      (node (ref "J4") (pin "24") (pinfunction "24_24") (pintype "passive"))
      (node (ref "J4") (pin "26") (pinfunction "26_26") (pintype "passive"))
      (node (ref "J4") (pin "28") (pinfunction "28_28") (pintype "passive"))
      (node (ref "J4") (pin "32") (pinfunction "32_32") (pintype "passive"))
      (node (ref "J4") (pin "34") (pinfunction "34_34") (pintype "passive"))
      (node (ref "J4") (pin "36") (pinfunction "36_36") (pintype "passive"))
      (node (ref "J4") (pin "38") (pinfunction "38_38") (pintype "passive"))
      (node (ref "J4") (pin "4") (pinfunction "4_4") (pintype "passive"))
      (node (ref "J4") (pin "40") (pinfunction "40_40") (pintype "passive"))
      (node (ref "J4") (pin "42") (pinfunction "42_42") (pintype "passive"))
      (node (ref "J4") (pin "44") (pinfunction "44_44") (pintype "passive"))
      (node (ref "J4") (pin "46") (pinfunction "46_46") (pintype "passive"))
      (node (ref "J4") (pin "48") (pinfunction "48_48") (pintype "passive"))
      (node (ref "J4") (pin "50") (pinfunction "50_50") (pintype "passive"))
      (node (ref "J4") (pin "52") (pinfunction "52_52") (pintype "passive"))
      (node (ref "J4") (pin "54") (pinfunction "54_54") (pintype "passive"))
      (node (ref "J4") (pin "56") (pinfunction "56_56") (pintype "passive"))
      (node (ref "J4") (pin "58") (pinfunction "58_58") (pintype "passive"))
      (node (ref "J4") (pin "6") (pinfunction "6_6") (pintype "passive"))
      (node (ref "J4") (pin "62") (pinfunction "62_62") (pintype "passive"))
      (node (ref "J4") (pin "66") (pinfunction "66_66") (pintype "passive"))
      (node (ref "J4") (pin "68") (pinfunction "68_68") (pintype "passive"))
      (node (ref "J4") (pin "8") (pinfunction "8_8") (pintype "passive"))
      (node (ref "J5") (pin "10") (pinfunction "10_10") (pintype "passive"))
      (node (ref "J5") (pin "12") (pinfunction "12_12") (pintype "passive"))
      (node (ref "J5") (pin "14") (pinfunction "14_14") (pintype "passive"))
      (node (ref "J5") (pin "16") (pinfunction "16_16") (pintype "passive"))
      (node (ref "J5") (pin "18") (pinfunction "18_18") (pintype "passive"))
      (node (ref "J5") (pin "2") (pinfunction "2_2") (pintype "passive"))
      (node (ref "J5") (pin "20") (pinfunction "20_20") (pintype "passive"))
      (node (ref "J5") (pin "22") (pinfunction "22_22") (pintype "passive"))
      (node (ref "J5") (pin "24") (pinfunction "24_24") (pintype "passive"))
      (node (ref "J5") (pin "26") (pinfunction "26_26") (pintype "passive"))
      (node (ref "J5") (pin "28") (pinfunction "28_28") (pintype "passive"))
      (node (ref "J5") (pin "32") (pinfunction "32_32") (pintype "passive"))
      (node (ref "J5") (pin "34") (pinfunction "34_34") (pintype "passive"))
      (node (ref "J5") (pin "36") (pinfunction "36_36") (pintype "passive"))
      (node (ref "J5") (pin "38") (pinfunction "38_38") (pintype "passive"))
      (node (ref "J5") (pin "4") (pinfunction "4_4") (pintype "passive"))
      (node (ref "J5") (pin "40") (pinfunction "40_40") (pintype "passive"))
      (node (ref "J5") (pin "42") (pinfunction "42_42") (pintype "passive"))
      (node (ref "J5") (pin "44") (pinfunction "44_44") (pintype "passive"))
      (node (ref "J5") (pin "46") (pinfunction "46_46") (pintype "passive"))
      (node (ref "J5") (pin "48") (pinfunction "48_48") (pintype "passive"))
      (node (ref "J5") (pin "50") (pinfunction "50_50") (pintype "passive"))
      (node (ref "J5") (pin "52") (pinfunction "52_52") (pintype "passive"))
      (node (ref "J5") (pin "54") (pinfunction "54_54") (pintype "passive"))
      (node (ref "J5") (pin "56") (pinfunction "56_56") (pintype "passive"))
      (node (ref "J5") (pin "58") (pinfunction "58_58") (pintype "passive"))
      (node (ref "J5") (pin "6") (pinfunction "6_6") (pintype "passive"))
      (node (ref "J5") (pin "62") (pinfunction "62_62") (pintype "passive"))
      (node (ref "J5") (pin "66") (pinfunction "66_66") (pintype "passive"))
      (node (ref "J5") (pin "68") (pinfunction "68_68") (pintype "passive"))
      (node (ref "J5") (pin "8") (pinfunction "8_8") (pintype "passive"))
      (node (ref "J6") (pin "10") (pinfunction "10_10") (pintype "passive"))
      (node (ref "J6") (pin "12") (pinfunction "12_12") (pintype "passive"))
      (node (ref "J6") (pin "14") (pinfunction "14_14") (pintype "passive"))
      (node (ref "J6") (pin "16") (pinfunction "16_16") (pintype "passive"))
      (node (ref "J6") (pin "18") (pinfunction "18_18") (pintype "passive"))
      (node (ref "J6") (pin "2") (pinfunction "2_2") (pintype "passive"))
      (node (ref "J6") (pin "20") (pinfunction "20_20") (pintype "passive"))
      (node (ref "J6") (pin "22") (pinfunction "22_22") (pintype "passive"))
      (node (ref "J6") (pin "24") (pinfunction "24_24") (pintype "passive"))
      (node (ref "J6") (pin "26") (pinfunction "26_26") (pintype "passive"))
      (node (ref "J6") (pin "28") (pinfunction "28_28") (pintype "passive"))
      (node (ref "J6") (pin "32") (pinfunction "32_32") (pintype "passive"))
      (node (ref "J6") (pin "34") (pinfunction "34_34") (pintype "passive"))
      (node (ref "J6") (pin "36") (pinfunction "36_36") (pintype "passive"))
      (node (ref "J6") (pin "38") (pinfunction "38_38") (pintype "passive"))
      (node (ref "J6") (pin "4") (pinfunction "4_4") (pintype "passive"))
      (node (ref "J6") (pin "40") (pinfunction "40_40") (pintype "passive"))
      (node (ref "J6") (pin "42") (pinfunction "42_42") (pintype "passive"))
      (node (ref "J6") (pin "44") (pinfunction "44_44") (pintype "passive"))
      (node (ref "J6") (pin "46") (pinfunction "46_46") (pintype "passive"))
      (node (ref "J6") (pin "48") (pinfunction "48_48") (pintype "passive"))
      (node (ref "J6") (pin "50") (pinfunction "50_50") (pintype "passive"))
      (node (ref "J6") (pin "52") (pinfunction "52_52") (pintype "passive"))
      (node (ref "J6") (pin "54") (pinfunction "54_54") (pintype "passive"))
      (node (ref "J6") (pin "56") (pinfunction "56_56") (pintype "passive"))
      (node (ref "J6") (pin "58") (pinfunction "58_58") (pintype "passive"))
      (node (ref "J6") (pin "6") (pinfunction "6_6") (pintype "passive"))
      (node (ref "J6") (pin "62") (pinfunction "62_62") (pintype "passive"))
      (node (ref "J6") (pin "66") (pinfunction "66_66") (pintype "passive"))
      (node (ref "J6") (pin "68") (pinfunction "68_68") (pintype "passive"))
      (node (ref "J6") (pin "8") (pinfunction "8_8") (pintype "passive"))
    )
    (net (code "205") (name "unconnected-(J1-Pad33)") (class "Default")
      (node (ref "J1") (pin "33") (pinfunction "33_33") (pintype "passive"))
    )
    (net (code "206") (name "unconnected-(J1-PadMH1)") (class "Default")
      (node (ref "J1") (pin "MH1") (pinfunction "MH1_MH1") (pintype "passive"))
    )
    (net (code "207") (name "unconnected-(J1-PadMH2)") (class "Default")
      (node (ref "J1") (pin "MH2") (pinfunction "MH2_MH2") (pintype "passive"))
    )
    (net (code "208") (name "unconnected-(J1-PadMP1)") (class "Default")
      (node (ref "J1") (pin "MP1") (pinfunction "MP1_MP1") (pintype "passive"))
    )
    (net (code "209") (name "unconnected-(J1-PadMP2)") (class "Default")
      (node (ref "J1") (pin "MP2") (pinfunction "MP2_MP2") (pintype "passive"))
    )
    (net (code "210") (name "unconnected-(J2-Pad33)") (class "Default")
      (node (ref "J2") (pin "33") (pinfunction "33_33") (pintype "passive"))
    )
    (net (code "211") (name "unconnected-(J2-PadMH1)") (class "Default")
      (node (ref "J2") (pin "MH1") (pinfunction "MH1_MH1") (pintype "passive"))
    )
    (net (code "212") (name "unconnected-(J2-PadMH2)") (class "Default")
      (node (ref "J2") (pin "MH2") (pinfunction "MH2_MH2") (pintype "passive"))
    )
    (net (code "213") (name "unconnected-(J2-PadMP1)") (class "Default")
      (node (ref "J2") (pin "MP1") (pinfunction "MP1_MP1") (pintype "passive"))
    )
    (net (code "214") (name "unconnected-(J2-PadMP2)") (class "Default")
      (node (ref "J2") (pin "MP2") (pinfunction "MP2_MP2") (pintype "passive"))
    )
    (net (code "215") (name "unconnected-(J3-Pad33)") (class "Default")
      (node (ref "J3") (pin "33") (pinfunction "33_33") (pintype "passive"))
    )
    (net (code "216") (name "unconnected-(J3-PadMH1)") (class "Default")
      (node (ref "J3") (pin "MH1") (pinfunction "MH1_MH1") (pintype "passive"))
    )
    (net (code "217") (name "unconnected-(J3-PadMH2)") (class "Default")
      (node (ref "J3") (pin "MH2") (pinfunction "MH2_MH2") (pintype "passive"))
    )
    (net (code "218") (name "unconnected-(J3-PadMP1)") (class "Default")
      (node (ref "J3") (pin "MP1") (pinfunction "MP1_MP1") (pintype "passive"))
    )
    (net (code "219") (name "unconnected-(J3-PadMP2)") (class "Default")
      (node (ref "J3") (pin "MP2") (pinfunction "MP2_MP2") (pintype "passive"))
    )
    (net (code "220") (name "unconnected-(J4-Pad33)") (class "Default")
      (node (ref "J4") (pin "33") (pinfunction "33_33") (pintype "passive"))
    )
    (net (code "221") (name "unconnected-(J4-PadMH1)") (class "Default")
      (node (ref "J4") (pin "MH1") (pinfunction "MH1_MH1") (pintype "passive"))
    )
    (net (code "222") (name "unconnected-(J4-PadMH2)") (class "Default")
      (node (ref "J4") (pin "MH2") (pinfunction "MH2_MH2") (pintype "passive"))
    )
    (net (code "223") (name "unconnected-(J4-PadMP1)") (class "Default")
      (node (ref "J4") (pin "MP1") (pinfunction "MP1_MP1") (pintype "passive"))
    )
    (net (code "224") (name "unconnected-(J4-PadMP2)") (class "Default")
      (node (ref "J4") (pin "MP2") (pinfunction "MP2_MP2") (pintype "passive"))
    )
    (net (code "225") (name "unconnected-(J5-Pad33)") (class "Default")
      (node (ref "J5") (pin "33") (pinfunction "33_33") (pintype "passive"))
    )
    (net (code "226") (name "unconnected-(J5-PadMH1)") (class "Default")
      (node (ref "J5") (pin "MH1") (pinfunction "MH1_MH1") (pintype "passive"))
    )
    (net (code "227") (name "unconnected-(J5-PadMH2)") (class "Default")
      (node (ref "J5") (pin "MH2") (pinfunction "MH2_MH2") (pintype "passive"))
    )
    (net (code "228") (name "unconnected-(J5-PadMP1)") (class "Default")
      (node (ref "J5") (pin "MP1") (pinfunction "MP1_MP1") (pintype "passive"))
    )
    (net (code "229") (name "unconnected-(J5-PadMP2)") (class "Default")
      (node (ref "J5") (pin "MP2") (pinfunction "MP2_MP2") (pintype "passive"))
    )
    (net (code "230") (name "unconnected-(J6-Pad33)") (class "Default")
      (node (ref "J6") (pin "33") (pinfunction "33_33") (pintype "passive"))
    )
    (net (code "231") (name "unconnected-(J6-Pad35)") (class "Default")
      (node (ref "J6") (pin "35") (pinfunction "35_35") (pintype "passive"))
    )
    (net (code "232") (name "unconnected-(J6-PadMH1)") (class "Default")
      (node (ref "J6") (pin "MH1") (pinfunction "MH1_MH1") (pintype "passive"))
    )
    (net (code "233") (name "unconnected-(J6-PadMH2)") (class "Default")
      (node (ref "J6") (pin "MH2") (pinfunction "MH2_MH2") (pintype "passive"))
    )
    (net (code "234") (name "unconnected-(J6-PadMP1)") (class "Default")
      (node (ref "J6") (pin "MP1") (pinfunction "MP1_MP1") (pintype "passive"))
    )
    (net (code "235") (name "unconnected-(J6-PadMP2)") (class "Default")
      (node (ref "J6") (pin "MP2") (pinfunction "MP2_MP2") (pintype "passive"))
    )
  )
)
